# Sheet_dual.net
KiCad netlist of a schematic drawn in Altium Designer
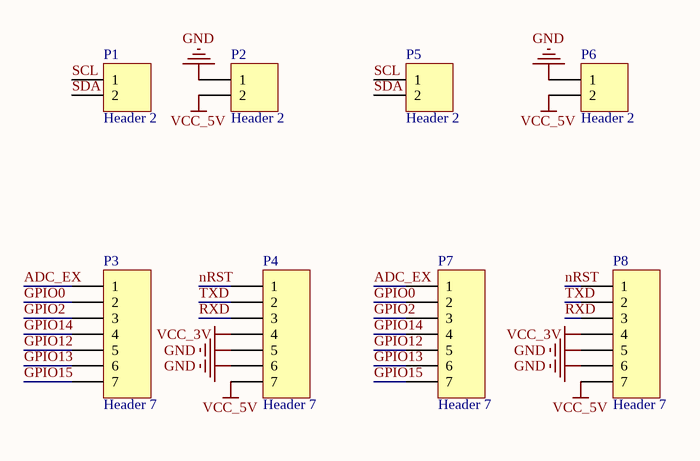
[diagram p0: Sheet_dual.SchDoc]

(export (version "E")
  (design (tool "Eeschema 10.0.6"))
  (components
    (comp (ref "P1")
      (value "Header 2")
      (footprint "HDR1X2")
      (description "Header, 2-Pin")
      (fields (field (name "PUBLISHER") "Altium Limited"))
      (libsource (lib "Miscellaneous Connectors") (part "Header 2"))
    )
    (comp (ref "P2")
      (value "Header 2")
      (footprint "HDR1X2")
      (description "Header, 2-Pin")
      (fields (field (name "PUBLISHER") "Altium Limited"))
      (libsource (lib "Miscellaneous Connectors") (part "Header 2"))
    )
    (comp (ref "P3")
      (value "Header 7")
      (footprint "HDR1X7")
      (description "Header, 7-Pin")
      (fields (field (name "PUBLISHER") "Altium Limited"))
      (libsource (lib "Miscellaneous Connectors") (part "Header 7"))
    )
    (comp (ref "P4")
      (value "Header 7")
      (footprint "HDR1X7")
      (description "Header, 7-Pin")
      (fields (field (name "PUBLISHER") "Altium Limited"))
      (libsource (lib "Miscellaneous Connectors") (part "Header 7"))
    )
    (comp (ref "P5")
      (value "Header 2")
      (footprint "HDR1X2")
      (description "Header, 2-Pin")
      (fields (field (name "PUBLISHER") "Altium Limited"))
      (libsource (lib "Miscellaneous Connectors") (part "Header 2"))
    )
    (comp (ref "P6")
      (value "Header 2")
      (footprint "HDR1X2")
      (description "Header, 2-Pin")
      (fields (field (name "PUBLISHER") "Altium Limited"))
      (libsource (lib "Miscellaneous Connectors") (part "Header 2"))
    )
    (comp (ref "P7")
      (value "Header 7")
      (footprint "HDR1X7")
      (description "Header, 7-Pin")
      (fields (field (name "PUBLISHER") "Altium Limited"))
      (libsource (lib "Miscellaneous Connectors") (part "Header 7"))
    )
    (comp (ref "P8")
      (value "Header 7")
      (footprint "HDR1X7")
      (description "Header, 7-Pin")
      (fields (field (name "PUBLISHER") "Altium Limited"))
      (libsource (lib "Miscellaneous Connectors") (part "Header 7"))
    )
  )
  (nets
    (net (code "1") (name "/ADC_EX") (class "Default")
      (node (ref "P3") (pin "1") (pinfunction "1_1") (pintype "passive"))
      (node (ref "P7") (pin "1") (pinfunction "1_1") (pintype "passive"))
    )
    (net (code "2") (name "/GPIO0") (class "Default")
      (node (ref "P3") (pin "2") (pinfunction "2_2") (pintype "passive"))
      (node (ref "P7") (pin "2") (pinfunction "2_2") (pintype "passive"))
    )
    (net (code "3") (name "/GPIO2") (class "Default")
      (node (ref "P3") (pin "3") (pinfunction "3_3") (pintype "passive"))
      (node (ref "P7") (pin "3") (pinfunction "3_3") (pintype "passive"))
    )
    (net (code "4") (name "/GPIO12") (class "Default")
      (node (ref "P3") (pin "5") (pinfunction "5_5") (pintype "passive"))
      (node (ref "P7") (pin "5") (pinfunction "5_5") (pintype "passive"))
    )
    (net (code "5") (name "/GPIO13") (class "Default")
      (node (ref "P3") (pin "6") (pinfunction "6_6") (pintype "passive"))
      (node (ref "P7") (pin "6") (pinfunction "6_6") (pintype "passive"))
    )
    (net (code "6") (name "/GPIO14") (class "Default")
      (node (ref "P3") (pin "4") (pinfunction "4_4") (pintype "passive"))
      (node (ref "P7") (pin "4") (pinfunction "4_4") (pintype "passive"))
    )
    (net (code "7") (name "/GPIO15") (class "Default")
      (node (ref "P3") (pin "7") (pinfunction "7_7") (pintype "passive"))
      (node (ref "P7") (pin "7") (pinfunction "7_7") (pintype "passive"))
    )
    (net (code "8") (name "/RXD") (class "Default")
      (node (ref "P4") (pin "3") (pinfunction "3_3") (pintype "passive"))
      (node (ref "P8") (pin "3") (pinfunction "3_3") (pintype "passive"))
    )
    (net (code "9") (name "/SCL") (class "Default")
      (node (ref "P1") (pin "1") (pinfunction "1_1") (pintype "passive"))
      (node (ref "P5") (pin "1") (pinfunction "1_1") (pintype "passive"))
    )
    (net (code "10") (name "/SDA") (class "Default")
      (node (ref "P1") (pin "2") (pinfunction "2_2") (pintype "passive"))
      (node (ref "P5") (pin "2") (pinfunction "2_2") (pintype "passive"))
    )
    (net (code "11") (name "/TXD") (class "Default")
      (node (ref "P4") (pin "2") (pinfunction "2_2") (pintype "passive"))
      (node (ref "P8") (pin "2") (pinfunction "2_2") (pintype "passive"))
    )
    (net (code "12") (name "/nRST") (class "Default")
      (node (ref "P4") (pin "1") (pinfunction "1_1") (pintype "passive"))
      (node (ref "P8") (pin "1") (pinfunction "1_1") (pintype "passive"))
    )
    (net (code "13") (name "GND") (class "Default")
      (node (ref "P2") (pin "1") (pinfunction "1_1") (pintype "passive"))
      (node (ref "P4") (pin "5") (pinfunction "5_5") (pintype "passive"))
      (node (ref "P4") (pin "6") (pinfunction "6_6") (pintype "passive"))
      (node (ref "P6") (pin "1") (pinfunction "1_1") (pintype "passive"))
      (node (ref "P8") (pin "5") (pinfunction "5_5") (pintype "passive"))
      (node (ref "P8") (pin "6") (pinfunction "6_6") (pintype "passive"))
    )
    (net (code "14") (name "VCC_3V") (class "Default")
      (node (ref "P4") (pin "4") (pinfunction "4_4") (pintype "passive"))
      (node (ref "P8") (pin "4") (pinfunction "4_4") (pintype "passive"))
    )
    (net (code "15") (name "VCC_5V") (class "Default")
      (node (ref "P2") (pin "2") (pinfunction "2_2") (pintype "passive"))
      (node (ref "P4") (pin "7") (pinfunction "7_7") (pintype "passive"))
      (node (ref "P6") (pin "2") (pinfunction "2_2") (pintype "passive"))
      (node (ref "P8") (pin "7") (pinfunction "7_7") (pintype "passive"))
    )
  )
)
